# ARE_entrenadora_modular_doblecara_bis.net
KiCad netlist of a schematic drawn in EAGLE
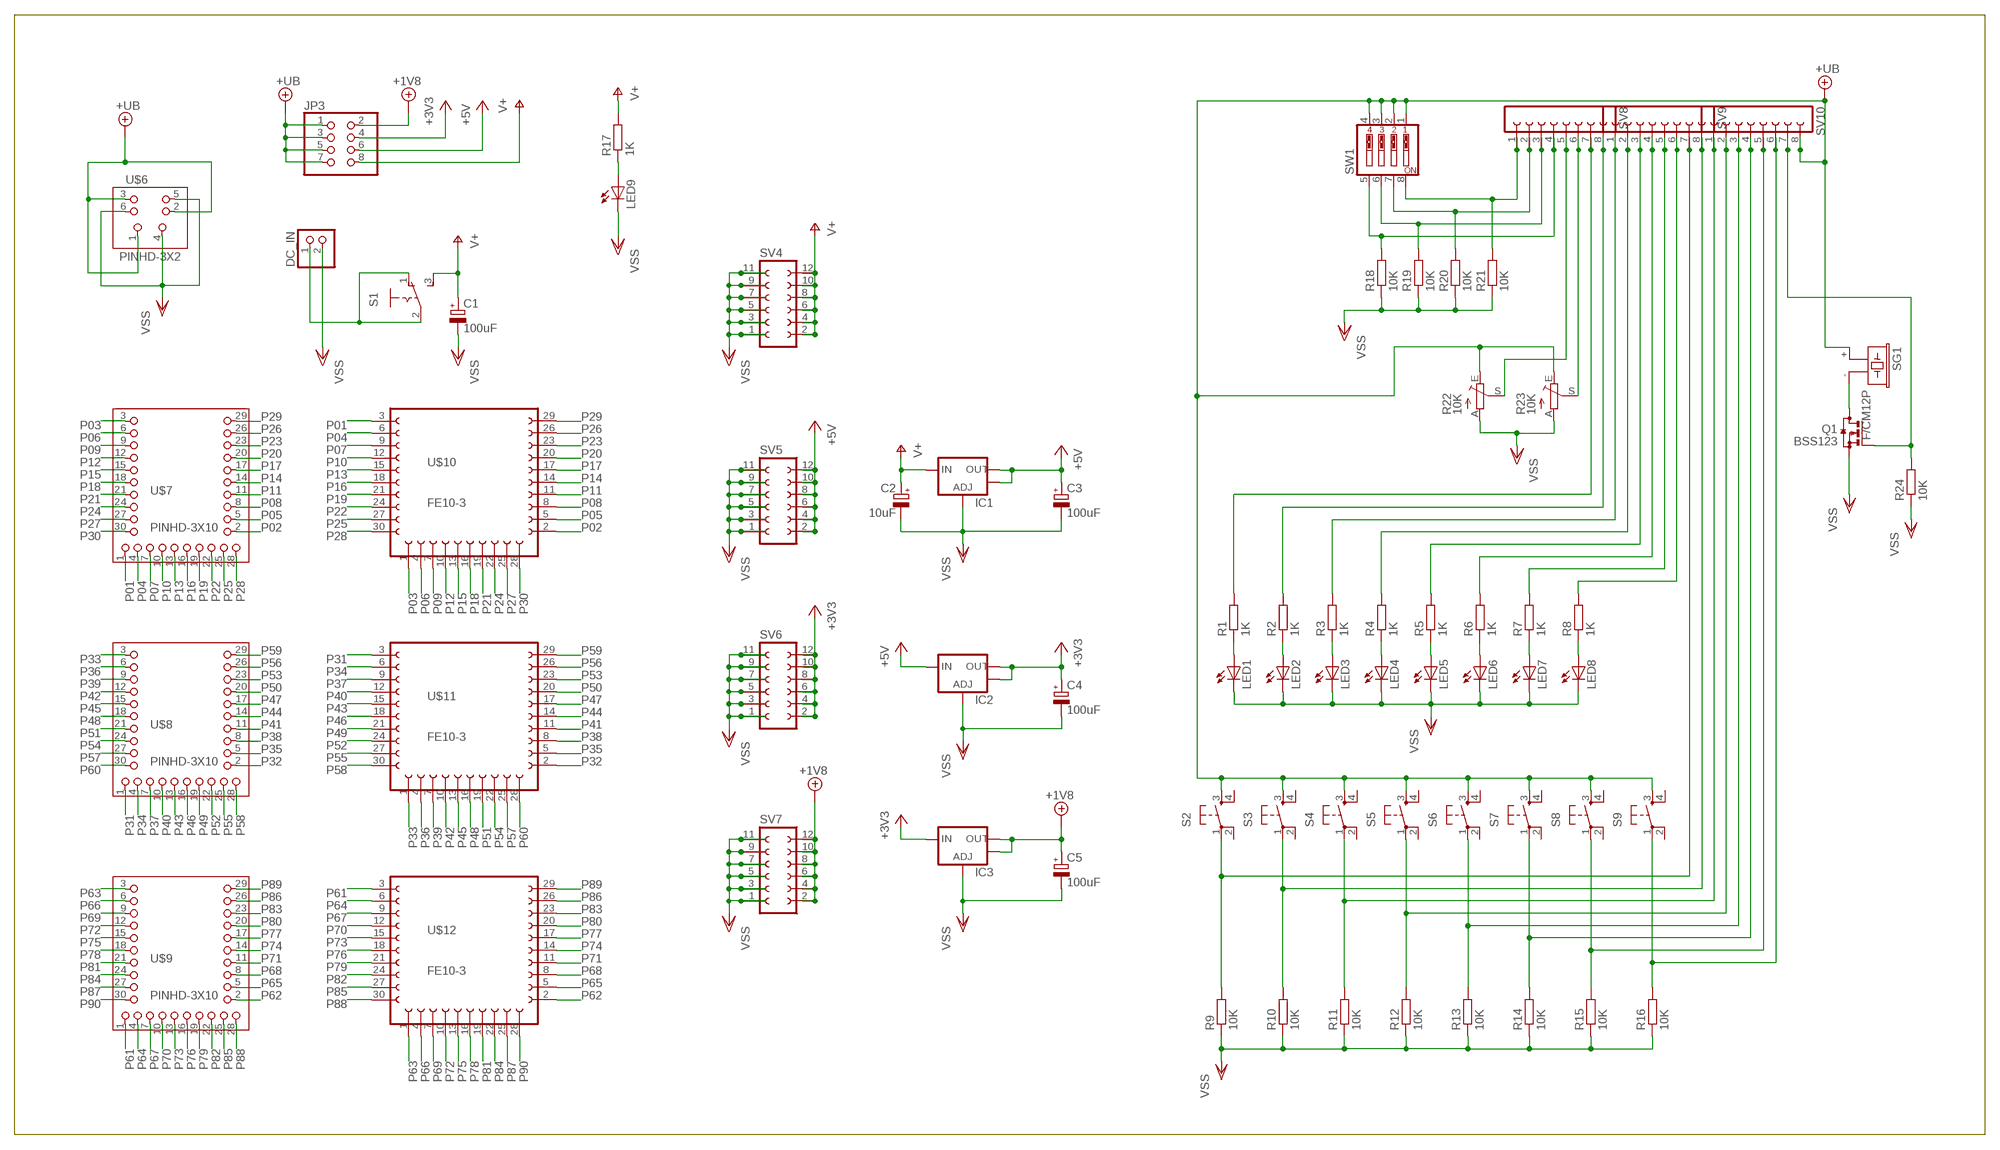
[diagram p0: schematic, sheet 1]

(export (version "E")
  (design (tool "Eeschema 10.0.6"))
  (components
    (comp (ref "C1")
      (value "100uF")
      (footprint "eagle-import:E2,5-6")
      (libsource (lib "eagle-import") (part "CPOL-EUE2.5-6"))
    )
    (comp (ref "C2")
      (value "10uF")
      (footprint "eagle-import:SMC_C")
      (libsource (lib "eagle-import") (part "CPOL-EUSMCC"))
    )
    (comp (ref "C3")
      (value "100uF")
      (footprint "eagle-import:CT7343")
      (libsource (lib "eagle-import") (part "CPOL-EUCT7343"))
    )
    (comp (ref "C4")
      (value "100uF")
      (footprint "eagle-import:CT7343")
      (libsource (lib "eagle-import") (part "CPOL-EUCT7343"))
    )
    (comp (ref "C5")
      (value "100uF")
      (footprint "eagle-import:CT7343")
      (libsource (lib "eagle-import") (part "CPOL-EUCT7343"))
    )
    (comp (ref "DC_IN")
      (value "PINHD-1X2/90")
      (footprint "eagle-import:1X02_90")
      (libsource (lib "eagle-import") (part "PINHD-1X2/90"))
    )
    (comp (ref "IC1")
      (value "V_REG_LM1117SOT223")
      (footprint "eagle-import:SOT223")
      (libsource (lib "eagle-import") (part "V_REG_LM1117SOT223"))
    )
    (comp (ref "IC2")
      (value "V_REG_LM1117SOT223")
      (footprint "eagle-import:SOT223")
      (libsource (lib "eagle-import") (part "V_REG_LM1117SOT223"))
    )
    (comp (ref "IC3")
      (value "V_REG_LM1117SOT223")
      (footprint "eagle-import:SOT223")
      (libsource (lib "eagle-import") (part "V_REG_LM1117SOT223"))
    )
    (comp (ref "JP3")
      (value "PINHD-2X4")
      (footprint "eagle-import:2X04")
      (libsource (lib "eagle-import") (part "PINHD-2X4"))
    )
    (comp (ref "LED1")
      (value "LEDCHIP-LED0805")
      (footprint "eagle-import:CHIP-LED0805")
      (libsource (lib "eagle-import") (part "LEDCHIP-LED0805"))
    )
    (comp (ref "LED2")
      (value "LEDCHIP-LED0805")
      (footprint "eagle-import:CHIP-LED0805")
      (libsource (lib "eagle-import") (part "LEDCHIP-LED0805"))
    )
    (comp (ref "LED3")
      (value "LEDCHIP-LED0805")
      (footprint "eagle-import:CHIP-LED0805")
      (libsource (lib "eagle-import") (part "LEDCHIP-LED0805"))
    )
    (comp (ref "LED4")
      (value "LEDCHIP-LED0805")
      (footprint "eagle-import:CHIP-LED0805")
      (libsource (lib "eagle-import") (part "LEDCHIP-LED0805"))
    )
    (comp (ref "LED5")
      (value "LEDCHIP-LED0805")
      (footprint "eagle-import:CHIP-LED0805")
      (libsource (lib "eagle-import") (part "LEDCHIP-LED0805"))
    )
    (comp (ref "LED6")
      (value "LEDCHIP-LED0805")
      (footprint "eagle-import:CHIP-LED0805")
      (libsource (lib "eagle-import") (part "LEDCHIP-LED0805"))
    )
    (comp (ref "LED7")
      (value "LEDCHIP-LED0805")
      (footprint "eagle-import:CHIP-LED0805")
      (libsource (lib "eagle-import") (part "LEDCHIP-LED0805"))
    )
    (comp (ref "LED8")
      (value "LEDCHIP-LED0805")
      (footprint "eagle-import:CHIP-LED0805")
      (libsource (lib "eagle-import") (part "LEDCHIP-LED0805"))
    )
    (comp (ref "LED9")
      (value "LEDCHIP-LED0805")
      (footprint "eagle-import:CHIP-LED0805")
      (libsource (lib "eagle-import") (part "LEDCHIP-LED0805"))
    )
    (comp (ref "Q1")
      (value "BSS123")
      (footprint "eagle-import:SOT23")
      (libsource (lib "eagle-import") (part "BSS123"))
    )
    (comp (ref "R1")
      (value "1K")
      (footprint "eagle-import:R0805")
      (libsource (lib "eagle-import") (part "R-EU_R0805"))
    )
    (comp (ref "R2")
      (value "1K")
      (footprint "eagle-import:R0805")
      (libsource (lib "eagle-import") (part "R-EU_R0805"))
    )
    (comp (ref "R3")
      (value "1K")
      (footprint "eagle-import:R0805")
      (libsource (lib "eagle-import") (part "R-EU_R0805"))
    )
    (comp (ref "R4")
      (value "1K")
      (footprint "eagle-import:R0805")
      (libsource (lib "eagle-import") (part "R-EU_R0805"))
    )
    (comp (ref "R5")
      (value "1K")
      (footprint "eagle-import:R0805")
      (libsource (lib "eagle-import") (part "R-EU_R0805"))
    )
    (comp (ref "R6")
      (value "1K")
      (footprint "eagle-import:R0805")
      (libsource (lib "eagle-import") (part "R-EU_R0805"))
    )
    (comp (ref "R7")
      (value "1K")
      (footprint "eagle-import:R0805")
      (libsource (lib "eagle-import") (part "R-EU_R0805"))
    )
    (comp (ref "R8")
      (value "1K")
      (footprint "eagle-import:R0805")
      (libsource (lib "eagle-import") (part "R-EU_R0805"))
    )
    (comp (ref "R9")
      (value "10K")
      (footprint "eagle-import:R0805")
      (libsource (lib "eagle-import") (part "R-EU_R0805"))
    )
    (comp (ref "R10")
      (value "10K")
      (footprint "eagle-import:R0805")
      (libsource (lib "eagle-import") (part "R-EU_R0805"))
    )
    (comp (ref "R11")
      (value "10K")
      (footprint "eagle-import:R0805")
      (libsource (lib "eagle-import") (part "R-EU_R0805"))
    )
    (comp (ref "R12")
      (value "10K")
      (footprint "eagle-import:R0805")
      (libsource (lib "eagle-import") (part "R-EU_R0805"))
    )
    (comp (ref "R13")
      (value "10K")
      (footprint "eagle-import:R0805")
      (libsource (lib "eagle-import") (part "R-EU_R0805"))
    )
    (comp (ref "R14")
      (value "10K")
      (footprint "eagle-import:R0805")
      (libsource (lib "eagle-import") (part "R-EU_R0805"))
    )
    (comp (ref "R15")
      (value "10K")
      (footprint "eagle-import:R0805")
      (libsource (lib "eagle-import") (part "R-EU_R0805"))
    )
    (comp (ref "R16")
      (value "10K")
      (footprint "eagle-import:R0805")
      (libsource (lib "eagle-import") (part "R-EU_R0805"))
    )
    (comp (ref "R17")
      (value "1K")
      (footprint "eagle-import:R0805")
      (libsource (lib "eagle-import") (part "R-EU_R0805"))
    )
    (comp (ref "R18")
      (value "10K")
      (footprint "eagle-import:R0805")
      (libsource (lib "eagle-import") (part "R-EU_R0805"))
    )
    (comp (ref "R19")
      (value "10K")
      (footprint "eagle-import:R0805")
      (libsource (lib "eagle-import") (part "R-EU_R0805"))
    )
    (comp (ref "R20")
      (value "10K")
      (footprint "eagle-import:R0805")
      (libsource (lib "eagle-import") (part "R-EU_R0805"))
    )
    (comp (ref "R21")
      (value "10K")
      (footprint "eagle-import:R0805")
      (libsource (lib "eagle-import") (part "R-EU_R0805"))
    )
    (comp (ref "R22")
      (value "10K")
      (footprint "eagle-import:CA6V")
      (libsource (lib "eagle-import") (part "TRIM_EU-CA6V"))
    )
    (comp (ref "R23")
      (value "10K")
      (footprint "eagle-import:CA6V")
      (libsource (lib "eagle-import") (part "TRIM_EU-CA6V"))
    )
    (comp (ref "R24")
      (value "10K")
      (footprint "eagle-import:R0805")
      (libsource (lib "eagle-import") (part "R-EU_R0805"))
    )
    (comp (ref "S1")
      (value "255SB")
      (footprint "eagle-import:255SB")
      (libsource (lib "eagle-import") (part "255SB"))
    )
    (comp (ref "S2")
      (value "TAC_SWITCHPTH")
      (footprint "eagle-import:TACTILE-PTH")
      (libsource (lib "eagle-import") (part "TAC_SWITCHPTH"))
    )
    (comp (ref "S3")
      (value "TAC_SWITCHPTH")
      (footprint "eagle-import:TACTILE-PTH")
      (libsource (lib "eagle-import") (part "TAC_SWITCHPTH"))
    )
    (comp (ref "S4")
      (value "TAC_SWITCHPTH")
      (footprint "eagle-import:TACTILE-PTH")
      (libsource (lib "eagle-import") (part "TAC_SWITCHPTH"))
    )
    (comp (ref "S5")
      (value "TAC_SWITCHPTH")
      (footprint "eagle-import:TACTILE-PTH")
      (libsource (lib "eagle-import") (part "TAC_SWITCHPTH"))
    )
    (comp (ref "S6")
      (value "TAC_SWITCHPTH")
      (footprint "eagle-import:TACTILE-PTH")
      (libsource (lib "eagle-import") (part "TAC_SWITCHPTH"))
    )
    (comp (ref "S7")
      (value "TAC_SWITCHPTH")
      (footprint "eagle-import:TACTILE-PTH")
      (libsource (lib "eagle-import") (part "TAC_SWITCHPTH"))
    )
    (comp (ref "S8")
      (value "TAC_SWITCHPTH")
      (footprint "eagle-import:TACTILE-PTH")
      (libsource (lib "eagle-import") (part "TAC_SWITCHPTH"))
    )
    (comp (ref "S9")
      (value "TAC_SWITCHPTH")
      (footprint "eagle-import:TACTILE-PTH")
      (libsource (lib "eagle-import") (part "TAC_SWITCHPTH"))
    )
    (comp (ref "SG1")
      (value "F/CM12P")
      (footprint "eagle-import:F_CM12P")
      (libsource (lib "eagle-import") (part "F/CM12P"))
    )
    (comp (ref "SV4")
      (value "FE06-2")
      (footprint "eagle-import:FE06-2")
      (libsource (lib "eagle-import") (part "FE06-2"))
    )
    (comp (ref "SV5")
      (value "FE06-2")
      (footprint "eagle-import:FE06-2")
      (libsource (lib "eagle-import") (part "FE06-2"))
    )
    (comp (ref "SV6")
      (value "FE06-2")
      (footprint "eagle-import:FE06-2")
      (libsource (lib "eagle-import") (part "FE06-2"))
    )
    (comp (ref "SV7")
      (value "FE06-2")
      (footprint "eagle-import:FE06-2")
      (libsource (lib "eagle-import") (part "FE06-2"))
    )
    (comp (ref "SV8")
      (value "FE08-1")
      (footprint "eagle-import:FE08")
      (libsource (lib "eagle-import") (part "FE08-1"))
    )
    (comp (ref "SV9")
      (value "FE08-1")
      (footprint "eagle-import:FE08")
      (libsource (lib "eagle-import") (part "FE08-1"))
    )
    (comp (ref "SV10")
      (value "FE08-1")
      (footprint "eagle-import:FE08")
      (libsource (lib "eagle-import") (part "FE08-1"))
    )
    (comp (ref "SW1")
      (value "SW_DIP-4")
      (footprint "eagle-import:EDG-04")
      (libsource (lib "eagle-import") (part "SW_DIP-4"))
    )
    (comp (ref "U$6")
      (value "PINHD-3X2")
      (footprint "eagle-import:3X02_90")
      (libsource (lib "eagle-import") (part "PINHD-3X2"))
    )
    (comp (ref "U$7")
      (value "PINHD-3X10")
      (footprint "eagle-import:3X10_90")
      (libsource (lib "eagle-import") (part "PINHD-3X10"))
    )
    (comp (ref "U$8")
      (value "PINHD-3X10")
      (footprint "eagle-import:3X10_90")
      (libsource (lib "eagle-import") (part "PINHD-3X10"))
    )
    (comp (ref "U$9")
      (value "PINHD-3X10")
      (footprint "eagle-import:3X10_90")
      (libsource (lib "eagle-import") (part "PINHD-3X10"))
    )
    (comp (ref "U$10")
      (value "FE10-3")
      (footprint "eagle-import:FE10-3")
      (libsource (lib "eagle-import") (part "FE10-3"))
    )
    (comp (ref "U$11")
      (value "FE10-3")
      (footprint "eagle-import:FE10-3")
      (libsource (lib "eagle-import") (part "FE10-3"))
    )
    (comp (ref "U$12")
      (value "FE10-3")
      (footprint "eagle-import:FE10-3")
      (libsource (lib "eagle-import") (part "FE10-3"))
    )
  )
  (nets
    (net (code "1") (name "+1V8") (class "Default")
      (node (ref "C5") (pin "+") (pinfunction "+_+") (pintype "passive"))
      (node (ref "IC3") (pin "2") (pinfunction "OUT_2") (pintype "output"))
      (node (ref "IC3") (pin "4") (pinfunction "OUT_4") (pintype "output"))
      (node (ref "JP3") (pin "2") (pinfunction "2_2") (pintype "passive"))
      (node (ref "SV7") (pin "10") (pinfunction "10_10") (pintype "passive"))
      (node (ref "SV7") (pin "12") (pinfunction "12_12") (pintype "passive"))
      (node (ref "SV7") (pin "2") (pinfunction "2_2") (pintype "passive"))
      (node (ref "SV7") (pin "4") (pinfunction "4_4") (pintype "passive"))
      (node (ref "SV7") (pin "6") (pinfunction "6_6") (pintype "passive"))
      (node (ref "SV7") (pin "8") (pinfunction "8_8") (pintype "passive"))
    )
    (net (code "2") (name "+3V3") (class "Default")
      (node (ref "C4") (pin "+") (pinfunction "+_+") (pintype "passive"))
      (node (ref "IC2") (pin "2") (pinfunction "OUT_2") (pintype "output"))
      (node (ref "IC2") (pin "4") (pinfunction "OUT_4") (pintype "output"))
      (node (ref "IC3") (pin "3") (pinfunction "IN_3") (pintype "input"))
      (node (ref "JP3") (pin "4") (pinfunction "4_4") (pintype "passive"))
      (node (ref "SV6") (pin "10") (pinfunction "10_10") (pintype "passive"))
      (node (ref "SV6") (pin "12") (pinfunction "12_12") (pintype "passive"))
      (node (ref "SV6") (pin "2") (pinfunction "2_2") (pintype "passive"))
      (node (ref "SV6") (pin "4") (pinfunction "4_4") (pintype "passive"))
      (node (ref "SV6") (pin "6") (pinfunction "6_6") (pintype "passive"))
      (node (ref "SV6") (pin "8") (pinfunction "8_8") (pintype "passive"))
    )
    (net (code "3") (name "+5V") (class "Default")
      (node (ref "C3") (pin "+") (pinfunction "+_+") (pintype "passive"))
      (node (ref "IC1") (pin "2") (pinfunction "OUT_2") (pintype "output"))
      (node (ref "IC1") (pin "4") (pinfunction "OUT_4") (pintype "output"))
      (node (ref "IC2") (pin "3") (pinfunction "IN_3") (pintype "input"))
      (node (ref "JP3") (pin "6") (pinfunction "6_6") (pintype "passive"))
      (node (ref "SV5") (pin "10") (pinfunction "10_10") (pintype "passive"))
      (node (ref "SV5") (pin "12") (pinfunction "12_12") (pintype "passive"))
      (node (ref "SV5") (pin "2") (pinfunction "2_2") (pintype "passive"))
      (node (ref "SV5") (pin "4") (pinfunction "4_4") (pintype "passive"))
      (node (ref "SV5") (pin "6") (pinfunction "6_6") (pintype "passive"))
      (node (ref "SV5") (pin "8") (pinfunction "8_8") (pintype "passive"))
    )
    (net (code "4") (name "+UB") (class "Default")
      (node (ref "JP3") (pin "1") (pinfunction "1_1") (pintype "passive"))
      (node (ref "JP3") (pin "3") (pinfunction "3_3") (pintype "passive"))
      (node (ref "JP3") (pin "5") (pinfunction "5_5") (pintype "passive"))
      (node (ref "JP3") (pin "7") (pinfunction "7_7") (pintype "passive"))
      (node (ref "R22") (pin "E") (pinfunction "E_E") (pintype "passive"))
      (node (ref "R23") (pin "E") (pinfunction "E_E") (pintype "passive"))
      (node (ref "S2") (pin "3") (pinfunction "3_3") (pintype "passive"))
      (node (ref "S3") (pin "3") (pinfunction "3_3") (pintype "passive"))
      (node (ref "S4") (pin "3") (pinfunction "3_3") (pintype "passive"))
      (node (ref "S5") (pin "3") (pinfunction "3_3") (pintype "passive"))
      (node (ref "S6") (pin "3") (pinfunction "3_3") (pintype "passive"))
      (node (ref "S7") (pin "3") (pinfunction "3_3") (pintype "passive"))
      (node (ref "S8") (pin "3") (pinfunction "3_3") (pintype "passive"))
      (node (ref "S9") (pin "3") (pinfunction "3_3") (pintype "passive"))
      (node (ref "SG1") (pin "+") (pinfunction "1_+") (pintype "passive"))
      (node (ref "SV10") (pin "8") (pinfunction "8_8") (pintype "passive"))
      (node (ref "SW1") (pin "1") (pinfunction "1_1") (pintype "passive"))
      (node (ref "SW1") (pin "2") (pinfunction "2_2") (pintype "passive"))
      (node (ref "SW1") (pin "3") (pinfunction "3_3") (pintype "passive"))
      (node (ref "SW1") (pin "4") (pinfunction "4_4") (pintype "passive"))
      (node (ref "U$6") (pin "1") (pinfunction "1_1") (pintype "passive"))
      (node (ref "U$6") (pin "2") (pinfunction "2_2") (pintype "passive"))
      (node (ref "U$6") (pin "3") (pinfunction "3_3") (pintype "passive"))
    )
    (net (code "5") (name "/P01") (class "Default")
      (node (ref "U$10") (pin "3") (pinfunction "3_3") (pintype "passive"))
      (node (ref "U$7") (pin "1") (pinfunction "1_1") (pintype "passive"))
    )
    (net (code "6") (name "/P02") (class "Default")
      (node (ref "U$10") (pin "2") (pinfunction "2_2") (pintype "passive"))
      (node (ref "U$7") (pin "2") (pinfunction "2_2") (pintype "passive"))
    )
    (net (code "7") (name "/P03") (class "Default")
      (node (ref "U$10") (pin "1") (pinfunction "1_1") (pintype "passive"))
      (node (ref "U$7") (pin "3") (pinfunction "3_3") (pintype "passive"))
    )
    (net (code "8") (name "/P04") (class "Default")
      (node (ref "U$10") (pin "6") (pinfunction "6_6") (pintype "passive"))
      (node (ref "U$7") (pin "4") (pinfunction "4_4") (pintype "passive"))
    )
    (net (code "9") (name "/P05") (class "Default")
      (node (ref "U$10") (pin "5") (pinfunction "5_5") (pintype "passive"))
      (node (ref "U$7") (pin "5") (pinfunction "5_5") (pintype "passive"))
    )
    (net (code "10") (name "/P06") (class "Default")
      (node (ref "U$10") (pin "4") (pinfunction "4_4") (pintype "passive"))
      (node (ref "U$7") (pin "6") (pinfunction "6_6") (pintype "passive"))
    )
    (net (code "11") (name "/P07") (class "Default")
      (node (ref "U$10") (pin "9") (pinfunction "9_9") (pintype "passive"))
      (node (ref "U$7") (pin "7") (pinfunction "7_7") (pintype "passive"))
    )
    (net (code "12") (name "/P08") (class "Default")
      (node (ref "U$10") (pin "8") (pinfunction "8_8") (pintype "passive"))
      (node (ref "U$7") (pin "8") (pinfunction "8_8") (pintype "passive"))
    )
    (net (code "13") (name "/P09") (class "Default")
      (node (ref "U$10") (pin "7") (pinfunction "7_7") (pintype "passive"))
      (node (ref "U$7") (pin "9") (pinfunction "9_9") (pintype "passive"))
    )
    (net (code "14") (name "/P10") (class "Default")
      (node (ref "U$10") (pin "12") (pinfunction "12_12") (pintype "passive"))
      (node (ref "U$7") (pin "10") (pinfunction "10_10") (pintype "passive"))
    )
    (net (code "15") (name "/P11") (class "Default")
      (node (ref "U$10") (pin "11") (pinfunction "11_11") (pintype "passive"))
      (node (ref "U$7") (pin "11") (pinfunction "11_11") (pintype "passive"))
    )
    (net (code "16") (name "/P12") (class "Default")
      (node (ref "U$10") (pin "10") (pinfunction "10_10") (pintype "passive"))
      (node (ref "U$7") (pin "12") (pinfunction "12_12") (pintype "passive"))
    )
    (net (code "17") (name "/P13") (class "Default")
      (node (ref "U$10") (pin "15") (pinfunction "15_15") (pintype "passive"))
      (node (ref "U$7") (pin "13") (pinfunction "13_13") (pintype "passive"))
    )
    (net (code "18") (name "/P14") (class "Default")
      (node (ref "U$10") (pin "14") (pinfunction "14_14") (pintype "passive"))
      (node (ref "U$7") (pin "14") (pinfunction "14_14") (pintype "passive"))
    )
    (net (code "19") (name "/P15") (class "Default")
      (node (ref "U$10") (pin "13") (pinfunction "13_13") (pintype "passive"))
      (node (ref "U$7") (pin "15") (pinfunction "15_15") (pintype "passive"))
    )
    (net (code "20") (name "/P16") (class "Default")
      (node (ref "U$10") (pin "18") (pinfunction "18_18") (pintype "passive"))
      (node (ref "U$7") (pin "16") (pinfunction "16_16") (pintype "passive"))
    )
    (net (code "21") (name "/P17") (class "Default")
      (node (ref "U$10") (pin "17") (pinfunction "17_17") (pintype "passive"))
      (node (ref "U$7") (pin "17") (pinfunction "17_17") (pintype "passive"))
    )
    (net (code "22") (name "/P18") (class "Default")
      (node (ref "U$10") (pin "16") (pinfunction "16_16") (pintype "passive"))
      (node (ref "U$7") (pin "18") (pinfunction "18_18") (pintype "passive"))
    )
    (net (code "23") (name "/P19") (class "Default")
      (node (ref "U$10") (pin "21") (pinfunction "21_21") (pintype "passive"))
      (node (ref "U$7") (pin "19") (pinfunction "19_19") (pintype "passive"))
    )
    (net (code "24") (name "/P20") (class "Default")
      (node (ref "U$10") (pin "20") (pinfunction "20_20") (pintype "passive"))
      (node (ref "U$7") (pin "20") (pinfunction "20_20") (pintype "passive"))
    )
    (net (code "25") (name "/P21") (class "Default")
      (node (ref "U$10") (pin "19") (pinfunction "19_19") (pintype "passive"))
      (node (ref "U$7") (pin "21") (pinfunction "21_21") (pintype "passive"))
    )
    (net (code "26") (name "/P22") (class "Default")
      (node (ref "U$10") (pin "24") (pinfunction "24_24") (pintype "passive"))
      (node (ref "U$7") (pin "22") (pinfunction "22_22") (pintype "passive"))
    )
    (net (code "27") (name "/P23") (class "Default")
      (node (ref "U$10") (pin "23") (pinfunction "23_23") (pintype "passive"))
      (node (ref "U$7") (pin "23") (pinfunction "23_23") (pintype "passive"))
    )
    (net (code "28") (name "/P24") (class "Default")
      (node (ref "U$10") (pin "22") (pinfunction "22_22") (pintype "passive"))
      (node (ref "U$7") (pin "24") (pinfunction "24_24") (pintype "passive"))
    )
    (net (code "29") (name "/P25") (class "Default")
      (node (ref "U$10") (pin "27") (pinfunction "27_27") (pintype "passive"))
      (node (ref "U$7") (pin "25") (pinfunction "25_25") (pintype "passive"))
    )
    (net (code "30") (name "/P26") (class "Default")
      (node (ref "U$10") (pin "26") (pinfunction "26_26") (pintype "passive"))
      (node (ref "U$7") (pin "26") (pinfunction "26_26") (pintype "passive"))
    )
    (net (code "31") (name "/P27") (class "Default")
      (node (ref "U$10") (pin "25") (pinfunction "25_25") (pintype "passive"))
      (node (ref "U$7") (pin "27") (pinfunction "27_27") (pintype "passive"))
    )
    (net (code "32") (name "/P28") (class "Default")
      (node (ref "U$10") (pin "30") (pinfunction "30_30") (pintype "passive"))
      (node (ref "U$7") (pin "28") (pinfunction "28_28") (pintype "passive"))
    )
    (net (code "33") (name "/P29") (class "Default")
      (node (ref "U$10") (pin "29") (pinfunction "29_29") (pintype "passive"))
      (node (ref "U$7") (pin "29") (pinfunction "29_29") (pintype "passive"))
    )
    (net (code "34") (name "/P30") (class "Default")
      (node (ref "U$10") (pin "28") (pinfunction "28_28") (pintype "passive"))
      (node (ref "U$7") (pin "30") (pinfunction "30_30") (pintype "passive"))
    )
    (net (code "35") (name "/P31") (class "Default")
      (node (ref "U$11") (pin "3") (pinfunction "3_3") (pintype "passive"))
      (node (ref "U$8") (pin "1") (pinfunction "1_1") (pintype "passive"))
    )
    (net (code "36") (name "/P32") (class "Default")
      (node (ref "U$11") (pin "2") (pinfunction "2_2") (pintype "passive"))
      (node (ref "U$8") (pin "2") (pinfunction "2_2") (pintype "passive"))
    )
    (net (code "37") (name "/P33") (class "Default")
      (node (ref "U$11") (pin "1") (pinfunction "1_1") (pintype "passive"))
      (node (ref "U$8") (pin "3") (pinfunction "3_3") (pintype "passive"))
    )
    (net (code "38") (name "/P34") (class "Default")
      (node (ref "U$11") (pin "6") (pinfunction "6_6") (pintype "passive"))
      (node (ref "U$8") (pin "4") (pinfunction "4_4") (pintype "passive"))
    )
    (net (code "39") (name "/P35") (class "Default")
      (node (ref "U$11") (pin "5") (pinfunction "5_5") (pintype "passive"))
      (node (ref "U$8") (pin "5") (pinfunction "5_5") (pintype "passive"))
    )
    (net (code "40") (name "/P36") (class "Default")
      (node (ref "U$11") (pin "4") (pinfunction "4_4") (pintype "passive"))
      (node (ref "U$8") (pin "6") (pinfunction "6_6") (pintype "passive"))
    )
    (net (code "41") (name "/P37") (class "Default")
      (node (ref "U$11") (pin "9") (pinfunction "9_9") (pintype "passive"))
      (node (ref "U$8") (pin "7") (pinfunction "7_7") (pintype "passive"))
    )
    (net (code "42") (name "/P38") (class "Default")
      (node (ref "U$11") (pin "8") (pinfunction "8_8") (pintype "passive"))
      (node (ref "U$8") (pin "8") (pinfunction "8_8") (pintype "passive"))
    )
    (net (code "43") (name "/P39") (class "Default")
      (node (ref "U$11") (pin "7") (pinfunction "7_7") (pintype "passive"))
      (node (ref "U$8") (pin "9") (pinfunction "9_9") (pintype "passive"))
    )
    (net (code "44") (name "/P40") (class "Default")
      (node (ref "U$11") (pin "12") (pinfunction "12_12") (pintype "passive"))
      (node (ref "U$8") (pin "10") (pinfunction "10_10") (pintype "passive"))
    )
    (net (code "45") (name "/P41") (class "Default")
      (node (ref "U$11") (pin "11") (pinfunction "11_11") (pintype "passive"))
      (node (ref "U$8") (pin "11") (pinfunction "11_11") (pintype "passive"))
    )
    (net (code "46") (name "/P42") (class "Default")
      (node (ref "U$11") (pin "10") (pinfunction "10_10") (pintype "passive"))
      (node (ref "U$8") (pin "12") (pinfunction "12_12") (pintype "passive"))
    )
    (net (code "47") (name "/P43") (class "Default")
      (node (ref "U$11") (pin "15") (pinfunction "15_15") (pintype "passive"))
      (node (ref "U$8") (pin "13") (pinfunction "13_13") (pintype "passive"))
    )
    (net (code "48") (name "/P44") (class "Default")
      (node (ref "U$11") (pin "14") (pinfunction "14_14") (pintype "passive"))
      (node (ref "U$8") (pin "14") (pinfunction "14_14") (pintype "passive"))
    )
    (net (code "49") (name "/P45") (class "Default")
      (node (ref "U$11") (pin "13") (pinfunction "13_13") (pintype "passive"))
      (node (ref "U$8") (pin "15") (pinfunction "15_15") (pintype "passive"))
    )
    (net (code "50") (name "/P46") (class "Default")
      (node (ref "U$11") (pin "18") (pinfunction "18_18") (pintype "passive"))
      (node (ref "U$8") (pin "16") (pinfunction "16_16") (pintype "passive"))
    )
    (net (code "51") (name "/P47") (class "Default")
      (node (ref "U$11") (pin "17") (pinfunction "17_17") (pintype "passive"))
      (node (ref "U$8") (pin "17") (pinfunction "17_17") (pintype "passive"))
    )
    (net (code "52") (name "/P48") (class "Default")
      (node (ref "U$11") (pin "16") (pinfunction "16_16") (pintype "passive"))
      (node (ref "U$8") (pin "18") (pinfunction "18_18") (pintype "passive"))
    )
    (net (code "53") (name "/P49") (class "Default")
      (node (ref "U$11") (pin "21") (pinfunction "21_21") (pintype "passive"))
      (node (ref "U$8") (pin "19") (pinfunction "19_19") (pintype "passive"))
    )
    (net (code "54") (name "/P50") (class "Default")
      (node (ref "U$11") (pin "20") (pinfunction "20_20") (pintype "passive"))
      (node (ref "U$8") (pin "20") (pinfunction "20_20") (pintype "passive"))
    )
    (net (code "55") (name "/P51") (class "Default")
      (node (ref "U$11") (pin "19") (pinfunction "19_19") (pintype "passive"))
      (node (ref "U$8") (pin "21") (pinfunction "21_21") (pintype "passive"))
    )
    (net (code "56") (name "/P52") (class "Default")
      (node (ref "U$11") (pin "24") (pinfunction "24_24") (pintype "passive"))
      (node (ref "U$8") (pin "22") (pinfunction "22_22") (pintype "passive"))
    )
    (net (code "57") (name "/P53") (class "Default")
      (node (ref "U$11") (pin "23") (pinfunction "23_23") (pintype "passive"))
      (node (ref "U$8") (pin "23") (pinfunction "23_23") (pintype "passive"))
    )
    (net (code "58") (name "/P54") (class "Default")
      (node (ref "U$11") (pin "22") (pinfunction "22_22") (pintype "passive"))
      (node (ref "U$8") (pin "24") (pinfunction "24_24") (pintype "passive"))
    )
    (net (code "59") (name "/P55") (class "Default")
      (node (ref "U$11") (pin "27") (pinfunction "27_27") (pintype "passive"))
      (node (ref "U$8") (pin "25") (pinfunction "25_25") (pintype "passive"))
    )
    (net (code "60") (name "/P56") (class "Default")
      (node (ref "U$11") (pin "26") (pinfunction "26_26") (pintype "passive"))
      (node (ref "U$8") (pin "26") (pinfunction "26_26") (pintype "passive"))
    )
    (net (code "61") (name "/P57") (class "Default")
      (node (ref "U$11") (pin "25") (pinfunction "25_25") (pintype "passive"))
      (node (ref "U$8") (pin "27") (pinfunction "27_27") (pintype "passive"))
    )
    (net (code "62") (name "/P58") (class "Default")
      (node (ref "U$11") (pin "30") (pinfunction "30_30") (pintype "passive"))
      (node (ref "U$8") (pin "28") (pinfunction "28_28") (pintype "passive"))
    )
    (net (code "63") (name "/P59") (class "Default")
      (node (ref "U$11") (pin "29") (pinfunction "29_29") (pintype "passive"))
      (node (ref "U$8") (pin "29") (pinfunction "29_29") (pintype "passive"))
    )
    (net (code "64") (name "/P60") (class "Default")
      (node (ref "U$11") (pin "28") (pinfunction "28_28") (pintype "passive"))
      (node (ref "U$8") (pin "30") (pinfunction "30_30") (pintype "passive"))
    )
    (net (code "65") (name "/P61") (class "Default")
      (node (ref "U$12") (pin "3") (pinfunction "3_3") (pintype "passive"))
      (node (ref "U$9") (pin "1") (pinfunction "1_1") (pintype "passive"))
    )
    (net (code "66") (name "/P62") (class "Default")
      (node (ref "U$12") (pin "2") (pinfunction "2_2") (pintype "passive"))
      (node (ref "U$9") (pin "2") (pinfunction "2_2") (pintype "passive"))
    )
    (net (code "67") (name "/P63") (class "Default")
      (node (ref "U$12") (pin "1") (pinfunction "1_1") (pintype "passive"))
      (node (ref "U$9") (pin "3") (pinfunction "3_3") (pintype "passive"))
    )
    (net (code "68") (name "/P64") (class "Default")
      (node (ref "U$12") (pin "6") (pinfunction "6_6") (pintype "passive"))
      (node (ref "U$9") (pin "4") (pinfunction "4_4") (pintype "passive"))
    )
    (net (code "69") (name "/P65") (class "Default")
      (node (ref "U$12") (pin "5") (pinfunction "5_5") (pintype "passive"))
      (node (ref "U$9") (pin "5") (pinfunction "5_5") (pintype "passive"))
    )
    (net (code "70") (name "/P66") (class "Default")
      (node (ref "U$12") (pin "4") (pinfunction "4_4") (pintype "passive"))
      (node (ref "U$9") (pin "6") (pinfunction "6_6") (pintype "passive"))
    )
    (net (code "71") (name "/P67") (class "Default")
      (node (ref "U$12") (pin "9") (pinfunction "9_9") (pintype "passive"))
      (node (ref "U$9") (pin "7") (pinfunction "7_7") (pintype "passive"))
    )
    (net (code "72") (name "/P68") (class "Default")
      (node (ref "U$12") (pin "8") (pinfunction "8_8") (pintype "passive"))
      (node (ref "U$9") (pin "8") (pinfunction "8_8") (pintype "passive"))
    )
    (net (code "73") (name "/P69") (class "Default")
      (node (ref "U$12") (pin "7") (pinfunction "7_7") (pintype "passive"))
      (node (ref "U$9") (pin "9") (pinfunction "9_9") (pintype "passive"))
    )
    (net (code "74") (name "/P70") (class "Default")
      (node (ref "U$12") (pin "12") (pinfunction "12_12") (pintype "passive"))
      (node (ref "U$9") (pin "10") (pinfunction "10_10") (pintype "passive"))
    )
    (net (code "75") (name "/P71") (class "Default")
      (node (ref "U$12") (pin "11") (pinfunction "11_11") (pintype "passive"))
      (node (ref "U$9") (pin "11") (pinfunction "11_11") (pintype "passive"))
    )
    (net (code "76") (name "/P72") (class "Default")
      (node (ref "U$12") (pin "10") (pinfunction "10_10") (pintype "passive"))
      (node (ref "U$9") (pin "12") (pinfunction "12_12") (pintype "passive"))
    )
    (net (code "77") (name "/P73") (class "Default")
      (node (ref "U$12") (pin "15") (pinfunction "15_15") (pintype "passive"))
      (node (ref "U$9") (pin "13") (pinfunction "13_13") (pintype "passive"))
    )
    (net (code "78") (name "/P74") (class "Default")
      (node (ref "U$12") (pin "14") (pinfunction "14_14") (pintype "passive"))
      (node (ref "U$9") (pin "14") (pinfunction "14_14") (pintype "passive"))
    )
    (net (code "79") (name "/P75") (class "Default")
      (node (ref "U$12") (pin "13") (pinfunction "13_13") (pintype "passive"))
      (node (ref "U$9") (pin "15") (pinfunction "15_15") (pintype "passive"))
    )
    (net (code "80") (name "/P76") (class "Default")
      (node (ref "U$12") (pin "18") (pinfunction "18_18") (pintype "passive"))
      (node (ref "U$9") (pin "16") (pinfunction "16_16") (pintype "passive"))
    )
    (net (code "81") (name "/P77") (class "Default")
      (node (ref "U$12") (pin "17") (pinfunction "17_17") (pintype "passive"))
      (node (ref "U$9") (pin "17") (pinfunction "17_17") (pintype "passive"))
    )
    (net (code "82") (name "/P78") (class "Default")
      (node (ref "U$12") (pin "16") (pinfunction "16_16") (pintype "passive"))
      (node (ref "U$9") (pin "18") (pinfunction "18_18") (pintype "passive"))
    )
    (net (code "83") (name "/P79") (class "Default")
      (node (ref "U$12") (pin "21") (pinfunction "21_21") (pintype "passive"))
      (node (ref "U$9") (pin "19") (pinfunction "19_19") (pintype "passive"))
    )
    (net (code "84") (name "/P80") (class "Default")
      (node (ref "U$12") (pin "20") (pinfunction "20_20") (pintype "passive"))
      (node (ref "U$9") (pin "20") (pinfunction "20_20") (pintype "passive"))
    )
    (net (code "85") (name "/P81") (class "Default")
      (node (ref "U$12") (pin "19") (pinfunction "19_19") (pintype "passive"))
      (node (ref "U$9") (pin "21") (pinfunction "21_21") (pintype "passive"))
    )
    (net (code "86") (name "/P82") (class "Default")
      (node (ref "U$12") (pin "24") (pinfunction "24_24") (pintype "passive"))
      (node (ref "U$9") (pin "22") (pinfunction "22_22") (pintype "passive"))
    )
    (net (code "87") (name "/P83") (class "Default")
      (node (ref "U$12") (pin "23") (pinfunction "23_23") (pintype "passive"))
      (node (ref "U$9") (pin "23") (pinfunction "23_23") (pintype "passive"))
    )
    (net (code "88") (name "/P84") (class "Default")
      (node (ref "U$12") (pin "22") (pinfunction "22_22") (pintype "passive"))
      (node (ref "U$9") (pin "24") (pinfunction "24_24") (pintype "passive"))
    )
    (net (code "89") (name "/P85") (class "Default")
      (node (ref "U$12") (pin "27") (pinfunction "27_27") (pintype "passive"))
      (node (ref "U$9") (pin "25") (pinfunction "25_25") (pintype "passive"))
    )
    (net (code "90") (name "/P86") (class "Default")
      (node (ref "U$12") (pin "26") (pinfunction "26_26") (pintype "passive"))
      (node (ref "U$9") (pin "26") (pinfunction "26_26") (pintype "passive"))
    )
    (net (code "91") (name "/P87") (class "Default")
      (node (ref "U$12") (pin "25") (pinfunction "25_25") (pintype "passive"))
      (node (ref "U$9") (pin "27") (pinfunction "27_27") (pintype "passive"))
    )
    (net (code "92") (name "/P88") (class "Default")
      (node (ref "U$12") (pin "30") (pinfunction "30_30") (pintype "passive"))
      (node (ref "U$9") (pin "28") (pinfunction "28_28") (pintype "passive"))
    )
    (net (code "93") (name "/P89") (class "Default")
      (node (ref "U$12") (pin "29") (pinfunction "29_29") (pintype "passive"))
      (node (ref "U$9") (pin "29") (pinfunction "29_29") (pintype "passive"))
    )
    (net (code "94") (name "/P90") (class "Default")
      (node (ref "U$12") (pin "28") (pinfunction "28_28") (pintype "passive"))
      (node (ref "U$9") (pin "30") (pinfunction "30_30") (pintype "passive"))
    )
    (net (code "95") (name "Net-(LED1-PadA)") (class "Default")
      (node (ref "LED1") (pin "A") (pinfunction "A_A") (pintype "passive"))
      (node (ref "R1") (pin "1") (pinfunction "1_1") (pintype "passive"))
    )
    (net (code "96") (name "Net-(LED2-PadA)") (class "Default")
      (node (ref "LED2") (pin "A") (pinfunction "A_A") (pintype "passive"))
      (node (ref "R2") (pin "1") (pinfunction "1_1") (pintype "passive"))
    )
    (net (code "97") (name "Net-(LED3-PadA)") (class "Default")
      (node (ref "LED3") (pin "A") (pinfunction "A_A") (pintype "passive"))
      (node (ref "R3") (pin "1") (pinfunction "1_1") (pintype "passive"))
    )
    (net (code "98") (name "Net-(LED4-PadA)") (class "Default")
      (node (ref "LED4") (pin "A") (pinfunction "A_A") (pintype "passive"))
      (node (ref "R4") (pin "1") (pinfunction "1_1") (pintype "passive"))
    )
    (net (code "99") (name "Net-(LED5-PadA)") (class "Default")
      (node (ref "LED5") (pin "A") (pinfunction "A_A") (pintype "passive"))
      (node (ref "R5") (pin "1") (pinfunction "1_1") (pintype "passive"))
    )
    (net (code "100") (name "Net-(LED6-PadA)") (class "Default")
      (node (ref "LED6") (pin "A") (pinfunction "A_A") (pintype "passive"))
      (node (ref "R6") (pin "1") (pinfunction "1_1") (pintype "passive"))
    )
    (net (code "101") (name "Net-(LED7-PadA)") (class "Default")
      (node (ref "LED7") (pin "A") (pinfunction "A_A") (pintype "passive"))
      (node (ref "R7") (pin "1") (pinfunction "1_1") (pintype "passive"))
    )
    (net (code "102") (name "Net-(LED8-PadA)") (class "Default")
      (node (ref "LED8") (pin "A") (pinfunction "A_A") (pintype "passive"))
      (node (ref "R8") (pin "1") (pinfunction "1_1") (pintype "passive"))
    )
    (net (code "103") (name "Net-(LED9-PadA)") (class "Default")
      (node (ref "LED9") (pin "A") (pinfunction "A_A") (pintype "passive"))
      (node (ref "R17") (pin "1") (pinfunction "1_1") (pintype "passive"))
    )
    (net (code "104") (name "Net-(Q1-D)") (class "Default")
      (node (ref "Q1") (pin "3") (pinfunction "D_3") (pintype "passive"))
      (node (ref "SG1") (pin "-") (pinfunction "2_-") (pintype "passive"))
    )
    (net (code "105") (name "Net-(Q1-G)") (class "Default")
      (node (ref "Q1") (pin "1") (pinfunction "G_1") (pintype "passive"))
      (node (ref "R24") (pin "2") (pinfunction "2_2") (pintype "passive"))
      (node (ref "SV10") (pin "7") (pinfunction "7_7") (pintype "passive"))
    )
    (net (code "106") (name "Net-(R1-Pad2)") (class "Default")
      (node (ref "R1") (pin "2") (pinfunction "2_2") (pintype "passive"))
      (node (ref "SV8") (pin "7") (pinfunction "7_7") (pintype "passive"))
    )
    (net (code "107") (name "Net-(R2-Pad2)") (class "Default")
      (node (ref "R2") (pin "2") (pinfunction "2_2") (pintype "passive"))
      (node (ref "SV8") (pin "8") (pinfunction "8_8") (pintype "passive"))
    )
    (net (code "108") (name "Net-(R3-Pad2)") (class "Default")
      (node (ref "R3") (pin "2") (pinfunction "2_2") (pintype "passive"))
      (node (ref "SV9") (pin "1") (pinfunction "1_1") (pintype "passive"))
    )
    (net (code "109") (name "Net-(R4-Pad2)") (class "Default")
      (node (ref "R4") (pin "2") (pinfunction "2_2") (pintype "passive"))
      (node (ref "SV9") (pin "2") (pinfunction "2_2") (pintype "passive"))
    )
    (net (code "110") (name "Net-(R5-Pad2)") (class "Default")
      (node (ref "R5") (pin "2") (pinfunction "2_2") (pintype "passive"))
      (node (ref "SV9") (pin "3") (pinfunction "3_3") (pintype "passive"))
    )
    (net (code "111") (name "Net-(R6-Pad2)") (class "Default")
      (node (ref "R6") (pin "2") (pinfunction "2_2") (pintype "passive"))
      (node (ref "SV9") (pin "4") (pinfunction "4_4") (pintype "passive"))
    )
    (net (code "112") (name "Net-(R7-Pad2)") (class "Default")
      (node (ref "R7") (pin "2") (pinfunction "2_2") (pintype "passive"))
      (node (ref "SV9") (pin "5") (pinfunction "5_5") (pintype "passive"))
    )
    (net (code "113") (name "Net-(R8-Pad2)") (class "Default")
      (node (ref "R8") (pin "2") (pinfunction "2_2") (pintype "passive"))
      (node (ref "SV9") (pin "6") (pinfunction "6_6") (pintype "passive"))
    )
    (net (code "114") (name "Net-(R9-Pad2)") (class "Default")
      (node (ref "R9") (pin "2") (pinfunction "2_2") (pintype "passive"))
      (node (ref "S2") (pin "1") (pinfunction "1_1") (pintype "passive"))
      (node (ref "SV9") (pin "7") (pinfunction "7_7") (pintype "passive"))
    )
    (net (code "115") (name "Net-(R10-Pad2)") (class "Default")
      (node (ref "R10") (pin "2") (pinfunction "2_2") (pintype "passive"))
      (node (ref "S3") (pin "1") (pinfunction "1_1") (pintype "passive"))
      (node (ref "SV9") (pin "8") (pinfunction "8_8") (pintype "passive"))
    )
    (net (code "116") (name "Net-(R11-Pad2)") (class "Default")
      (node (ref "R11") (pin "2") (pinfunction "2_2") (pintype "passive"))
      (node (ref "S4") (pin "1") (pinfunction "1_1") (pintype "passive"))
      (node (ref "SV10") (pin "1") (pinfunction "1_1") (pintype "passive"))
    )
    (net (code "117") (name "Net-(R12-Pad2)") (class "Default")
      (node (ref "R12") (pin "2") (pinfunction "2_2") (pintype "passive"))
      (node (ref "S5") (pin "1") (pinfunction "1_1") (pintype "passive"))
      (node (ref "SV10") (pin "2") (pinfunction "2_2") (pintype "passive"))
    )
    (net (code "118") (name "Net-(R13-Pad2)") (class "Default")
      (node (ref "R13") (pin "2") (pinfunction "2_2") (pintype "passive"))
      (node (ref "S6") (pin "1") (pinfunction "1_1") (pintype "passive"))
      (node (ref "SV10") (pin "3") (pinfunction "3_3") (pintype "passive"))
    )
    (net (code "119") (name "Net-(R14-Pad2)") (class "Default")
      (node (ref "R14") (pin "2") (pinfunction "2_2") (pintype "passive"))
      (node (ref "S7") (pin "1") (pinfunction "1_1") (pintype "passive"))
      (node (ref "SV10") (pin "4") (pinfunction "4_4") (pintype "passive"))
    )
    (net (code "120") (name "Net-(R15-Pad2)") (class "Default")
      (node (ref "R15") (pin "2") (pinfunction "2_2") (pintype "passive"))
      (node (ref "S8") (pin "1") (pinfunction "1_1") (pintype "passive"))
      (node (ref "SV10") (pin "5") (pinfunction "5_5") (pintype "passive"))
    )
    (net (code "121") (name "Net-(R16-Pad2)") (class "Default")
      (node (ref "R16") (pin "2") (pinfunction "2_2") (pintype "passive"))
      (node (ref "S9") (pin "1") (pinfunction "1_1") (pintype "passive"))
      (node (ref "SV10") (pin "6") (pinfunction "6_6") (pintype "passive"))
    )
    (net (code "122") (name "Net-(R18-Pad2)") (class "Default")
      (node (ref "R18") (pin "2") (pinfunction "2_2") (pintype "passive"))
      (node (ref "SV8") (pin "4") (pinfunction "4_4") (pintype "passive"))
      (node (ref "SW1") (pin "5") (pinfunction "5_5") (pintype "passive"))
    )
    (net (code "123") (name "Net-(R19-Pad2)") (class "Default")
      (node (ref "R19") (pin "2") (pinfunction "2_2") (pintype "passive"))
      (node (ref "SV8") (pin "3") (pinfunction "3_3") (pintype "passive"))
      (node (ref "SW1") (pin "6") (pinfunction "6_6") (pintype "passive"))
    )
    (net (code "124") (name "Net-(R20-Pad2)") (class "Default")
      (node (ref "R20") (pin "2") (pinfunction "2_2") (pintype "passive"))
      (node (ref "SV8") (pin "2") (pinfunction "2_2") (pintype "passive"))
      (node (ref "SW1") (pin "7") (pinfunction "7_7") (pintype "passive"))
    )
    (net (code "125") (name "Net-(R21-Pad2)") (class "Default")
      (node (ref "R21") (pin "2") (pinfunction "2_2") (pintype "passive"))
      (node (ref "SV8") (pin "1") (pinfunction "1_1") (pintype "passive"))
      (node (ref "SW1") (pin "8") (pinfunction "8_8") (pintype "passive"))
    )
    (net (code "126") (name "Net-(R22-PadS)") (class "Default")
      (node (ref "R22") (pin "S") (pinfunction "S_S") (pintype "passive"))
      (node (ref "SV8") (pin "5") (pinfunction "5_5") (pintype "passive"))
    )
    (net (code "127") (name "Net-(R23-PadS)") (class "Default")
      (node (ref "R23") (pin "S") (pinfunction "S_S") (pintype "passive"))
      (node (ref "SV8") (pin "6") (pinfunction "6_6") (pintype "passive"))
    )
    (net (code "128") (name "Net-(S1-O)") (class "Default")
      (node (ref "DC_IN") (pin "1") (pinfunction "1_1") (pintype "passive"))
      (node (ref "S1") (pin "1") (pinfunction "O_1") (pintype "passive"))
      (node (ref "S1") (pin "2") (pinfunction "P_2") (pintype "passive"))
    )
    (net (code "129") (name "V+") (class "Default")
      (node (ref "C1") (pin "+") (pinfunction "+_+") (pintype "passive"))
      (node (ref "C2") (pin "+") (pinfunction "+_+") (pintype "passive"))
      (node (ref "IC1") (pin "3") (pinfunction "IN_3") (pintype "input"))
      (node (ref "JP3") (pin "8") (pinfunction "8_8") (pintype "passive"))
      (node (ref "R17") (pin "2") (pinfunction "2_2") (pintype "passive"))
      (node (ref "S1") (pin "3") (pinfunction "S_3") (pintype "passive"))
      (node (ref "SV4") (pin "10") (pinfunction "10_10") (pintype "passive"))
      (node (ref "SV4") (pin "12") (pinfunction "12_12") (pintype "passive"))
      (node (ref "SV4") (pin "2") (pinfunction "2_2") (pintype "passive"))
      (node (ref "SV4") (pin "4") (pinfunction "4_4") (pintype "passive"))
      (node (ref "SV4") (pin "6") (pinfunction "6_6") (pintype "passive"))
      (node (ref "SV4") (pin "8") (pinfunction "8_8") (pintype "passive"))
    )
    (net (code "130") (name "VSS") (class "Default")
      (node (ref "C1") (pin "-") (pinfunction "-_-") (pintype "passive"))
      (node (ref "C2") (pin "-") (pinfunction "-_-") (pintype "passive"))
      (node (ref "C3") (pin "-") (pinfunction "-_-") (pintype "passive"))
      (node (ref "C4") (pin "-") (pinfunction "-_-") (pintype "passive"))
      (node (ref "C5") (pin "-") (pinfunction "-_-") (pintype "passive"))
      (node (ref "DC_IN") (pin "2") (pinfunction "2_2") (pintype "passive"))
      (node (ref "IC1") (pin "1") (pinfunction "ADJ_1") (pintype "input"))
      (node (ref "IC2") (pin "1") (pinfunction "ADJ_1") (pintype "input"))
      (node (ref "IC3") (pin "1") (pinfunction "ADJ_1") (pintype "input"))
      (node (ref "LED1") (pin "C") (pinfunction "C_C") (pintype "passive"))
      (node (ref "LED2") (pin "C") (pinfunction "C_C") (pintype "passive"))
      (node (ref "LED3") (pin "C") (pinfunction "C_C") (pintype "passive"))
      (node (ref "LED4") (pin "C") (pinfunction "C_C") (pintype "passive"))
      (node (ref "LED5") (pin "C") (pinfunction "C_C") (pintype "passive"))
      (node (ref "LED6") (pin "C") (pinfunction "C_C") (pintype "passive"))
      (node (ref "LED7") (pin "C") (pinfunction "C_C") (pintype "passive"))
      (node (ref "LED8") (pin "C") (pinfunction "C_C") (pintype "passive"))
      (node (ref "LED9") (pin "C") (pinfunction "C_C") (pintype "passive"))
      (node (ref "Q1") (pin "2") (pinfunction "S_2") (pintype "passive"))
      (node (ref "R10") (pin "1") (pinfunction "1_1") (pintype "passive"))
      (node (ref "R11") (pin "1") (pinfunction "1_1") (pintype "passive"))
      (node (ref "R12") (pin "1") (pinfunction "1_1") (pintype "passive"))
      (node (ref "R13") (pin "1") (pinfunction "1_1") (pintype "passive"))
      (node (ref "R14") (pin "1") (pinfunction "1_1") (pintype "passive"))
      (node (ref "R15") (pin "1") (pinfunction "1_1") (pintype "passive"))
      (node (ref "R16") (pin "1") (pinfunction "1_1") (pintype "passive"))
      (node (ref "R18") (pin "1") (pinfunction "1_1") (pintype "passive"))
      (node (ref "R19") (pin "1") (pinfunction "1_1") (pintype "passive"))
      (node (ref "R20") (pin "1") (pinfunction "1_1") (pintype "passive"))
      (node (ref "R21") (pin "1") (pinfunction "1_1") (pintype "passive"))
      (node (ref "R22") (pin "A") (pinfunction "A_A") (pintype "passive"))
      (node (ref "R23") (pin "A") (pinfunction "A_A") (pintype "passive"))
      (node (ref "R24") (pin "1") (pinfunction "1_1") (pintype "passive"))
      (node (ref "R9") (pin "1") (pinfunction "1_1") (pintype "passive"))
      (node (ref "SV4") (pin "1") (pinfunction "1_1") (pintype "passive"))
      (node (ref "SV4") (pin "11") (pinfunction "11_11") (pintype "passive"))
      (node (ref "SV4") (pin "3") (pinfunction "3_3") (pintype "passive"))
      (node (ref "SV4") (pin "5") (pinfunction "5_5") (pintype "passive"))
      (node (ref "SV4") (pin "7") (pinfunction "7_7") (pintype "passive"))
      (node (ref "SV4") (pin "9") (pinfunction "9_9") (pintype "passive"))
      (node (ref "SV5") (pin "1") (pinfunction "1_1") (pintype "passive"))
      (node (ref "SV5") (pin "11") (pinfunction "11_11") (pintype "passive"))
      (node (ref "SV5") (pin "3") (pinfunction "3_3") (pintype "passive"))
      (node (ref "SV5") (pin "5") (pinfunction "5_5") (pintype "passive"))
      (node (ref "SV5") (pin "7") (pinfunction "7_7") (pintype "passive"))
      (node (ref "SV5") (pin "9") (pinfunction "9_9") (pintype "passive"))
      (node (ref "SV6") (pin "1") (pinfunction "1_1") (pintype "passive"))
      (node (ref "SV6") (pin "11") (pinfunction "11_11") (pintype "passive"))
      (node (ref "SV6") (pin "3") (pinfunction "3_3") (pintype "passive"))
      (node (ref "SV6") (pin "5") (pinfunction "5_5") (pintype "passive"))
      (node (ref "SV6") (pin "7") (pinfunction "7_7") (pintype "passive"))
      (node (ref "SV6") (pin "9") (pinfunction "9_9") (pintype "passive"))
      (node (ref "SV7") (pin "1") (pinfunction "1_1") (pintype "passive"))
      (node (ref "SV7") (pin "11") (pinfunction "11_11") (pintype "passive"))
      (node (ref "SV7") (pin "3") (pinfunction "3_3") (pintype "passive"))
      (node (ref "SV7") (pin "5") (pinfunction "5_5") (pintype "passive"))
      (node (ref "SV7") (pin "7") (pinfunction "7_7") (pintype "passive"))
      (node (ref "SV7") (pin "9") (pinfunction "9_9") (pintype "passive"))
      (node (ref "U$6") (pin "4") (pinfunction "4_4") (pintype "passive"))
      (node (ref "U$6") (pin "5") (pinfunction "5_5") (pintype "passive"))
      (node (ref "U$6") (pin "6") (pinfunction "6_6") (pintype "passive"))
    )
    (net (code "131") (name "unconnected-(S2-Pad2)") (class "Default")
      (node (ref "S2") (pin "2") (pinfunction "2_2") (pintype "passive"))
    )
    (net (code "132") (name "unconnected-(S2-Pad4)") (class "Default")
      (node (ref "S2") (pin "4") (pinfunction "4_4") (pintype "passive"))
    )
    (net (code "133") (name "unconnected-(S3-Pad2)") (class "Default")
      (node (ref "S3") (pin "2") (pinfunction "2_2") (pintype "passive"))
    )
    (net (code "134") (name "unconnected-(S3-Pad4)") (class "Default")
      (node (ref "S3") (pin "4") (pinfunction "4_4") (pintype "passive"))
    )
    (net (code "135") (name "unconnected-(S4-Pad2)") (class "Default")
      (node (ref "S4") (pin "2") (pinfunction "2_2") (pintype "passive"))
    )
    (net (code "136") (name "unconnected-(S4-Pad4)") (class "Default")
      (node (ref "S4") (pin "4") (pinfunction "4_4") (pintype "passive"))
    )
    (net (code "137") (name "unconnected-(S5-Pad2)") (class "Default")
      (node (ref "S5") (pin "2") (pinfunction "2_2") (pintype "passive"))
    )
    (net (code "138") (name "unconnected-(S5-Pad4)") (class "Default")
      (node (ref "S5") (pin "4") (pinfunction "4_4") (pintype "passive"))
    )
    (net (code "139") (name "unconnected-(S6-Pad2)") (class "Default")
      (node (ref "S6") (pin "2") (pinfunction "2_2") (pintype "passive"))
    )
    (net (code "140") (name "unconnected-(S6-Pad4)") (class "Default")
      (node (ref "S6") (pin "4") (pinfunction "4_4") (pintype "passive"))
    )
    (net (code "141") (name "unconnected-(S7-Pad2)") (class "Default")
      (node (ref "S7") (pin "2") (pinfunction "2_2") (pintype "passive"))
    )
    (net (code "142") (name "unconnected-(S7-Pad4)") (class "Default")
      (node (ref "S7") (pin "4") (pinfunction "4_4") (pintype "passive"))
    )
    (net (code "143") (name "unconnected-(S8-Pad2)") (class "Default")
      (node (ref "S8") (pin "2") (pinfunction "2_2") (pintype "passive"))
    )
    (net (code "144") (name "unconnected-(S8-Pad4)") (class "Default")
      (node (ref "S8") (pin "4") (pinfunction "4_4") (pintype "passive"))
    )
    (net (code "145") (name "unconnected-(S9-Pad2)") (class "Default")
      (node (ref "S9") (pin "2") (pinfunction "2_2") (pintype "passive"))
    )
    (net (code "146") (name "unconnected-(S9-Pad4)") (class "Default")
      (node (ref "S9") (pin "4") (pinfunction "4_4") (pintype "passive"))
    )
  )
)
